# SOIC_Breakout_Solar.net
KiCad netlist of a schematic drawn in EAGLE
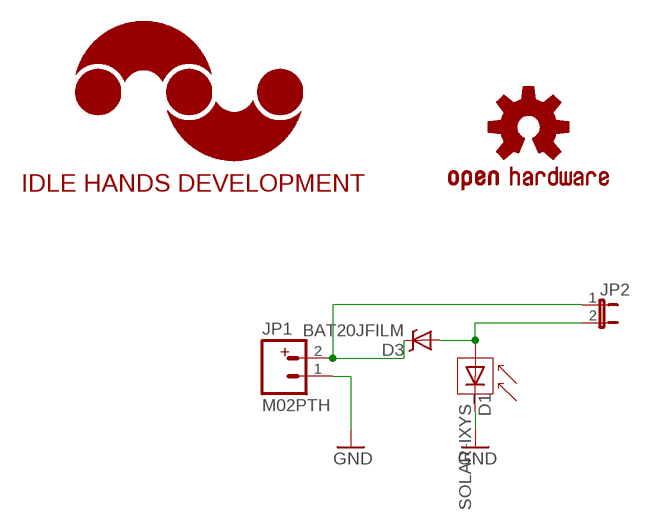
[diagram p0: schematic, sheet 1]

(export (version "E")
  (design (tool "Eeschema 10.0.6"))
  (components
    (comp (ref "D1")
      (value "SOLAR-IXYS_")
      (footprint "eagle-import:SO08")
      (libsource (lib "eagle-import") (part "SOLAR-IXYS_"))
    )
    (comp (ref "D3")
      (value "BAT20JFILM")
      (footprint "eagle-import:SOD-323")
      (libsource (lib "eagle-import") (part "BAT20JFILM"))
    )
    (comp (ref "JP1")
      (value "M02PTH")
      (footprint "eagle-import:1X02")
      (libsource (lib "eagle-import") (part "M02PTH"))
    )
    (comp (ref "JP2")
      (value "JUMPER-2SMD-NO")
      (footprint "eagle-import:SJ_2S-NO")
      (libsource (lib "eagle-import") (part "JUMPER-2SMD-NO"))
    )
    (comp (ref "LOGO1")
      (value "IDLEHANDS_LOGOS")
      (footprint "eagle-import:IHD-LOGO-S")
      (libsource (lib "eagle-import") (part "IDLEHANDS_LOGOS"))
    )
    (comp (ref "LOGO2")
      (value "OSHW-LOGOS")
      (footprint "eagle-import:OSHW-LOGO-S")
      (libsource (lib "eagle-import") (part "OSHW-LOGOS"))
    )
  )
  (nets
    (net (code "1") (name "GND") (class "Default")
      (node (ref "D1") (pin "5") (pinfunction "C_5") (pintype "passive"))
      (node (ref "JP1") (pin "1") (pinfunction "1_1") (pintype "passive"))
    )
    (net (code "2") (name "Net-(D1-A)") (class "Default")
      (node (ref "D1") (pin "8") (pinfunction "A_8") (pintype "passive"))
      (node (ref "D3") (pin "2") (pinfunction "A_2") (pintype "passive"))
      (node (ref "JP2") (pin "2") (pinfunction "2_2") (pintype "passive"))
    )
    (net (code "3") (name "Net-(D3-C)") (class "Default")
      (node (ref "D3") (pin "1") (pinfunction "C_1") (pintype "passive"))
      (node (ref "JP1") (pin "2") (pinfunction "2_2") (pintype "passive"))
      (node (ref "JP2") (pin "1") (pinfunction "1_1") (pintype "passive"))
    )
  )
)
